# FPGA_GTP.net
KiCad netlist of a schematic drawn in Altium Designer
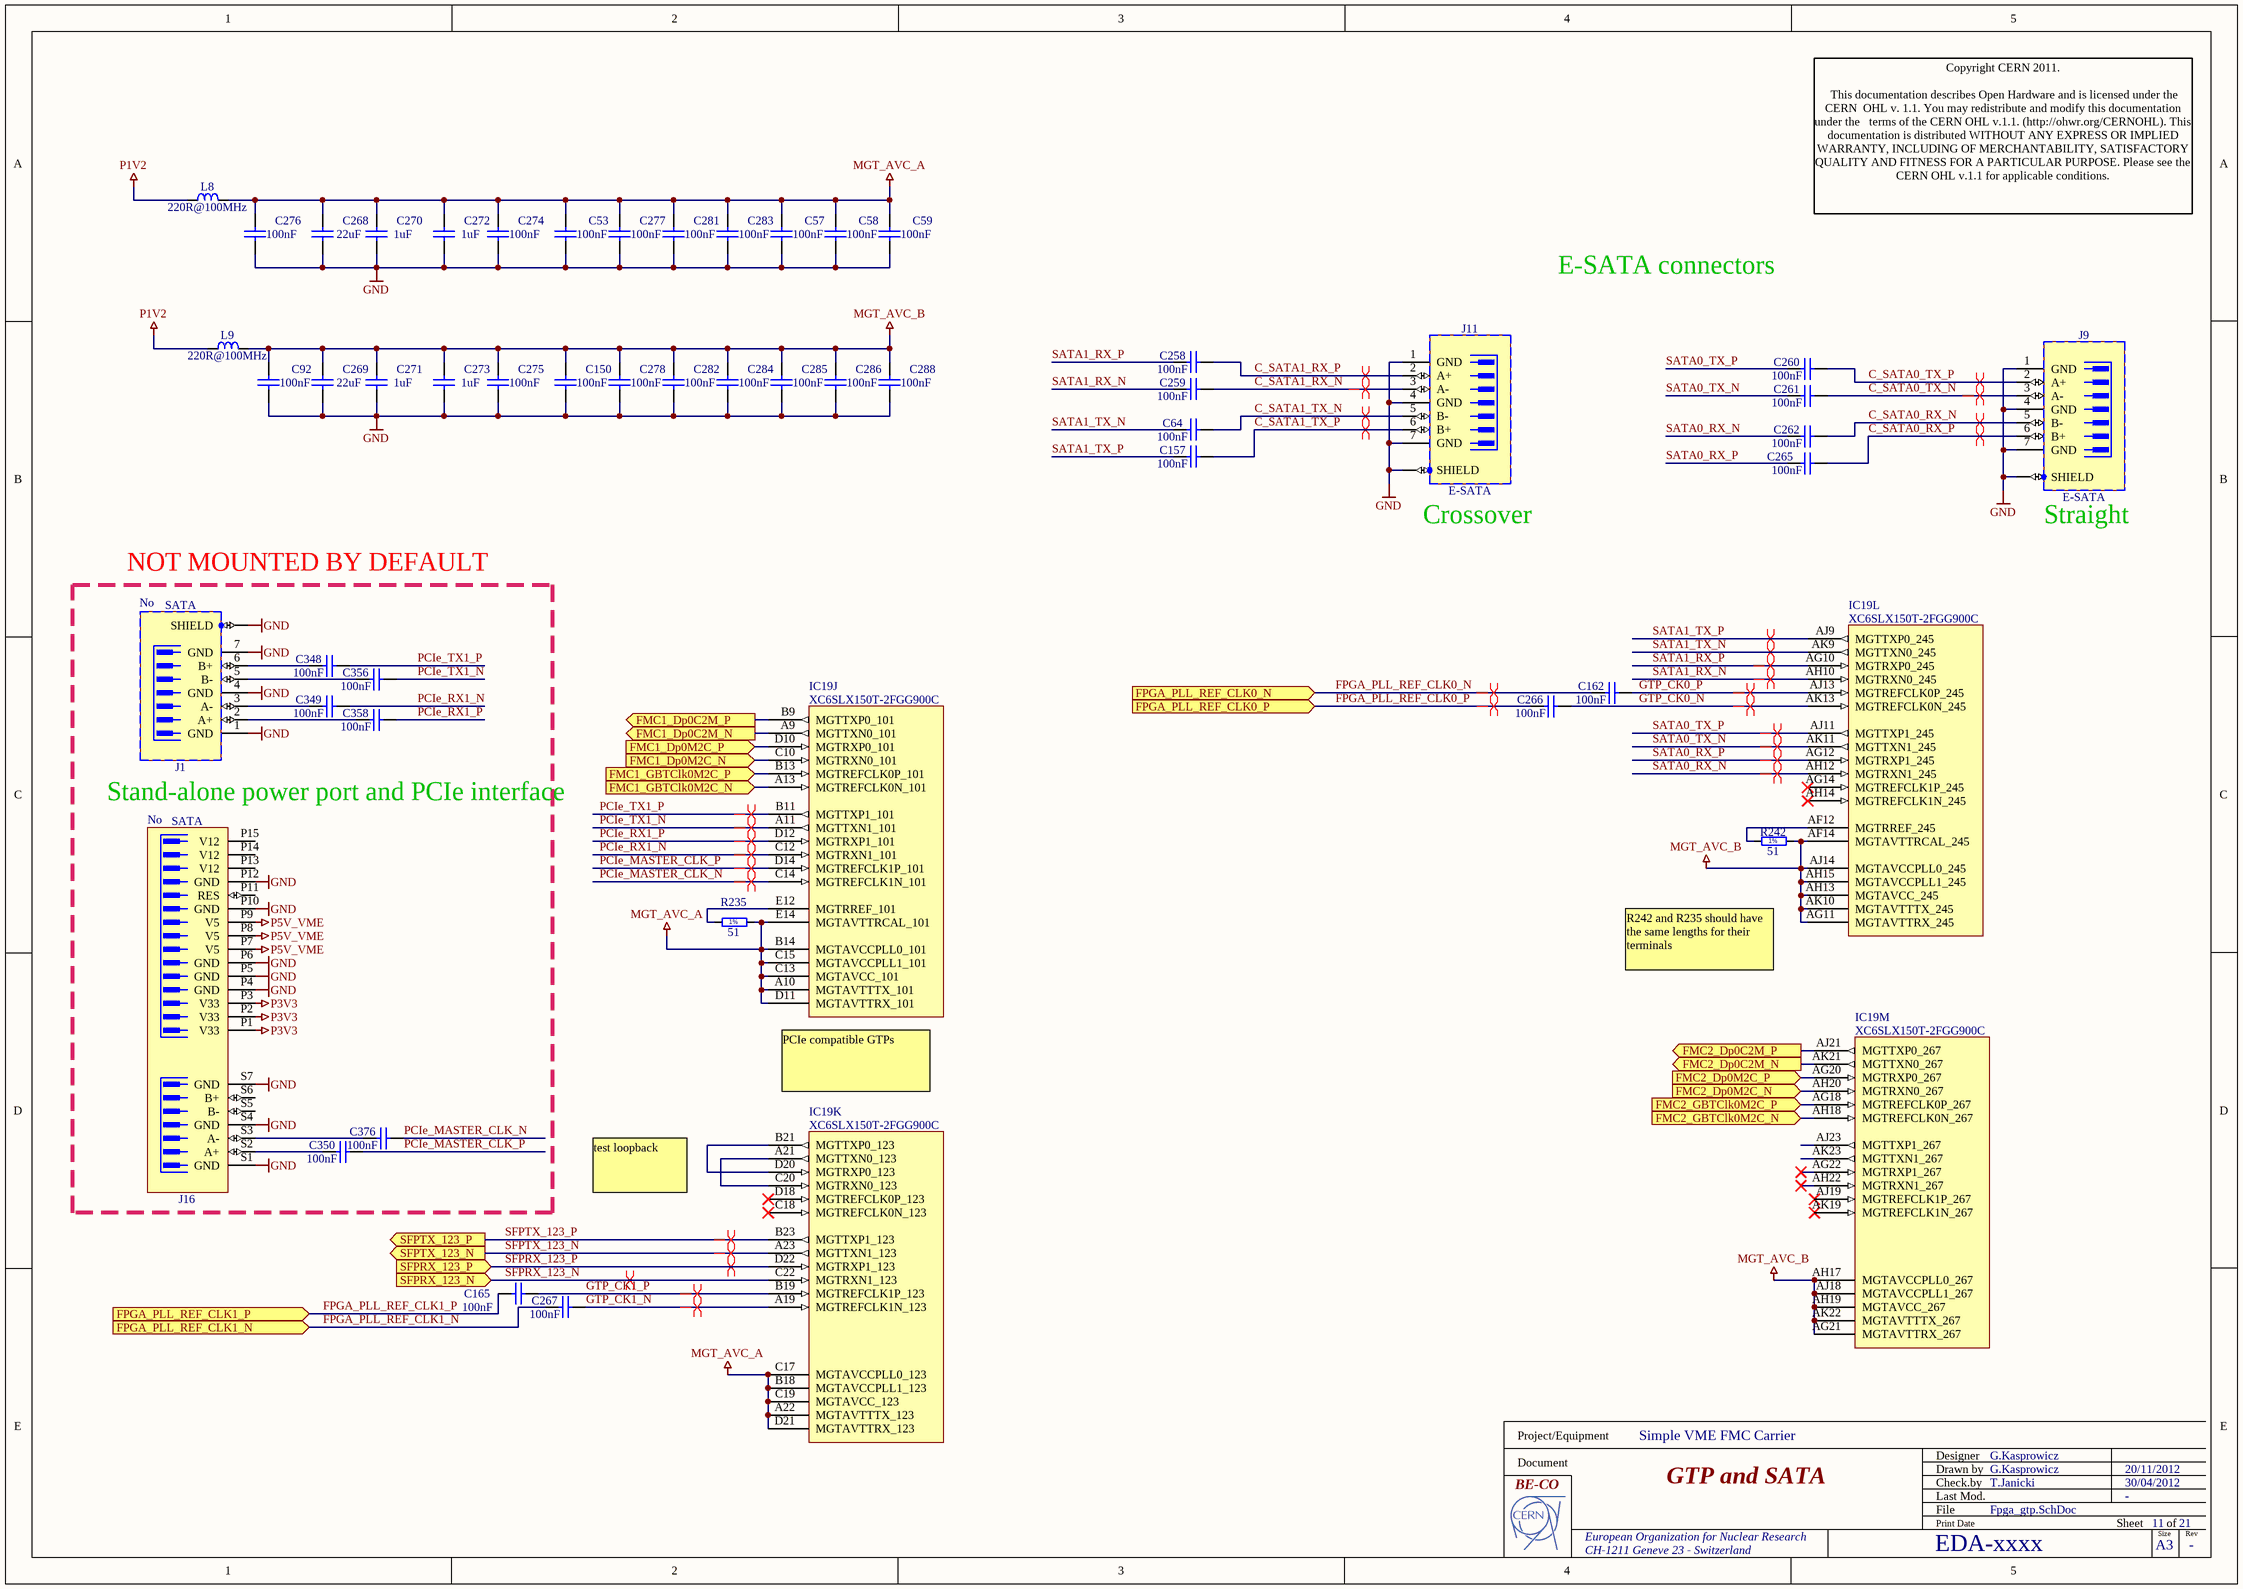
[diagram p0: FPGA_GTP.SchDoc]

(export (version "E")
  (design (tool "Eeschema 10.0.6"))
  (components
    (comp (ref "C53")
      (value "100nF")
      (footprint "CAPC1005X55N")
      (description "Non-polarised capacitor")
      (fields
        (field (name "PART NUMBER") "CC0402_100NF_16V_10%_X7R")
        (field (name "VOLTAGE") "16V")
        (field (name "AUTHOR") "CERN DEM JLC")
      )
      (libsource (lib "Capacitors") (part "Capacitor - non polarized"))
    )
    (comp (ref "C57")
      (value "100nF")
      (footprint "CAPC1005X55N")
      (description "Non-polarised capacitor")
      (fields
        (field (name "PART NUMBER") "CC0402_100NF_16V_10%_X7R")
        (field (name "VOLTAGE") "16V")
        (field (name "AUTHOR") "CERN DEM JLC")
      )
      (libsource (lib "Capacitors") (part "Capacitor - non polarized"))
    )
    (comp (ref "C58")
      (value "100nF")
      (footprint "CAPC1005X55N")
      (description "Non-polarised capacitor")
      (fields
        (field (name "PART NUMBER") "CC0402_100NF_16V_10%_X7R")
        (field (name "VOLTAGE") "16V")
        (field (name "AUTHOR") "CERN DEM JLC")
      )
      (libsource (lib "Capacitors") (part "Capacitor - non polarized"))
    )
    (comp (ref "C59")
      (value "100nF")
      (footprint "CAPC1005X55N")
      (description "Non-polarised capacitor")
      (fields
        (field (name "PART NUMBER") "CC0402_100NF_16V_10%_X7R")
        (field (name "VOLTAGE") "16V")
        (field (name "AUTHOR") "CERN DEM JLC")
      )
      (libsource (lib "Capacitors") (part "Capacitor - non polarized"))
    )
    (comp (ref "C64")
      (value "100nF")
      (footprint "CAPC1005X55N")
      (description "Non-polarised capacitor")
      (fields
        (field (name "PART NUMBER") "CC0402_100NF_16V_10%_X7R")
        (field (name "VOLTAGE") "16V")
        (field (name "AUTHOR") "CERN DEM JLC")
      )
      (libsource (lib "Capacitors") (part "Capacitor - non polarized"))
    )
    (comp (ref "C92")
      (value "100nF")
      (footprint "CAPC1005X55N")
      (description "Non-polarised capacitor")
      (fields
        (field (name "PART NUMBER") "CC0402_100NF_16V_10%_X7R")
        (field (name "VOLTAGE") "16V")
        (field (name "AUTHOR") "CERN DEM JLC")
      )
      (libsource (lib "Capacitors") (part "Capacitor - non polarized"))
    )
    (comp (ref "C150")
      (value "100nF")
      (footprint "CAPC1005X55N")
      (description "Non-polarised capacitor")
      (fields
        (field (name "PART NUMBER") "CC0402_100NF_16V_10%_X7R")
        (field (name "VOLTAGE") "16V")
        (field (name "AUTHOR") "CERN DEM JLC")
      )
      (libsource (lib "Capacitors") (part "Capacitor - non polarized"))
    )
    (comp (ref "C157")
      (value "100nF")
      (footprint "CAPC1005X55N")
      (description "Non-polarised capacitor")
      (fields
        (field (name "PART NUMBER") "CC0402_100NF_16V_10%_X7R")
        (field (name "VOLTAGE") "16V")
        (field (name "AUTHOR") "CERN DEM JLC")
      )
      (libsource (lib "Capacitors") (part "Capacitor - non polarized"))
    )
    (comp (ref "C162")
      (value "100nF")
      (footprint "CAPC1005X55N")
      (description "Non-polarised capacitor")
      (fields
        (field (name "PART NUMBER") "CC0402_100NF_16V_10%_X7R")
        (field (name "VOLTAGE") "16V")
        (field (name "AUTHOR") "CERN DEM JLC")
      )
      (libsource (lib "Capacitors") (part "Capacitor - non polarized"))
    )
    (comp (ref "C165")
      (value "100nF")
      (footprint "CAPC1005X55N")
      (description "Non-polarised capacitor")
      (fields
        (field (name "PART NUMBER") "CC0402_100NF_16V_10%_X7R")
        (field (name "VOLTAGE") "16V")
        (field (name "AUTHOR") "CERN DEM JLC")
      )
      (libsource (lib "Capacitors") (part "Capacitor - non polarized"))
    )
    (comp (ref "C258")
      (value "100nF")
      (footprint "CAPC1005X55N")
      (description "Non-polarised capacitor")
      (fields
        (field (name "PART NUMBER") "CC0402_100NF_16V_10%_X7R")
        (field (name "VOLTAGE") "16V")
        (field (name "AUTHOR") "CERN DEM JLC")
      )
      (libsource (lib "Capacitors") (part "Capacitor - non polarized"))
    )
    (comp (ref "C259")
      (value "100nF")
      (footprint "CAPC1005X55N")
      (description "Non-polarised capacitor")
      (fields
        (field (name "PART NUMBER") "CC0402_100NF_16V_10%_X7R")
        (field (name "VOLTAGE") "16V")
        (field (name "AUTHOR") "CERN DEM JLC")
      )
      (libsource (lib "Capacitors") (part "Capacitor - non polarized"))
    )
    (comp (ref "C260")
      (value "100nF")
      (footprint "CAPC1005X55N")
      (description "Non-polarised capacitor")
      (fields
        (field (name "PART NUMBER") "CC0402_100NF_16V_10%_X7R")
        (field (name "VOLTAGE") "16V")
        (field (name "AUTHOR") "CERN DEM JLC")
      )
      (libsource (lib "Capacitors") (part "Capacitor - non polarized"))
    )
    (comp (ref "C261")
      (value "100nF")
      (footprint "CAPC1005X55N")
      (description "Non-polarised capacitor")
      (fields
        (field (name "PART NUMBER") "CC0402_100NF_16V_10%_X7R")
        (field (name "VOLTAGE") "16V")
        (field (name "AUTHOR") "CERN DEM JLC")
      )
      (libsource (lib "Capacitors") (part "Capacitor - non polarized"))
    )
    (comp (ref "C262")
      (value "100nF")
      (footprint "CAPC1005X55N")
      (description "Non-polarised capacitor")
      (fields
        (field (name "PART NUMBER") "CC0402_100NF_16V_10%_X7R")
        (field (name "VOLTAGE") "16V")
        (field (name "AUTHOR") "CERN DEM JLC")
      )
      (libsource (lib "Capacitors") (part "Capacitor - non polarized"))
    )
    (comp (ref "C265")
      (value "100nF")
      (footprint "CAPC1005X55N")
      (description "Non-polarised capacitor")
      (fields
        (field (name "PART NUMBER") "CC0402_100NF_16V_10%_X7R")
        (field (name "VOLTAGE") "16V")
        (field (name "AUTHOR") "CERN DEM JLC")
      )
      (libsource (lib "Capacitors") (part "Capacitor - non polarized"))
    )
    (comp (ref "C266")
      (value "100nF")
      (footprint "CAPC1005X55N")
      (description "Non-polarised capacitor")
      (fields
        (field (name "PART NUMBER") "CC0402_100NF_16V_10%_X7R")
        (field (name "VOLTAGE") "16V")
        (field (name "AUTHOR") "CERN DEM JLC")
      )
      (libsource (lib "Capacitors") (part "Capacitor - non polarized"))
    )
    (comp (ref "C267")
      (value "100nF")
      (footprint "CAPC1005X55N")
      (description "Non-polarised capacitor")
      (fields
        (field (name "PART NUMBER") "CC0402_100NF_16V_10%_X7R")
        (field (name "VOLTAGE") "16V")
        (field (name "AUTHOR") "CERN DEM JLC")
      )
      (libsource (lib "Capacitors") (part "Capacitor - non polarized"))
    )
    (comp (ref "C268")
      (value "22uF")
      (footprint "CAPC3216X180N")
      (description "Non-polarised capacitor")
      (fields
        (field (name "PART NUMBER") "CC1206_22UF_10V_10%_X7R")
        (field (name "VOLTAGE") "10V")
        (field (name "AUTHOR") "CERN DEM JLC")
      )
      (libsource (lib "Capacitors") (part "Capacitor - non polarized"))
    )
    (comp (ref "C269")
      (value "22uF")
      (footprint "CAPC3216X180N")
      (description "Non-polarised capacitor")
      (fields
        (field (name "PART NUMBER") "CC1206_22UF_10V_10%_X7R")
        (field (name "VOLTAGE") "10V")
        (field (name "AUTHOR") "CERN DEM JLC")
      )
      (libsource (lib "Capacitors") (part "Capacitor - non polarized"))
    )
    (comp (ref "C270")
      (value "1uF")
      (footprint "CAPC1608X87N")
      (description "Non-polarised capacitor")
      (fields
        (field (name "PART NUMBER") "CC0603_1UF_16V_10%_X7R")
        (field (name "VOLTAGE") "16V")
        (field (name "AUTHOR") "CERN DEM JLC")
      )
      (libsource (lib "Capacitors") (part "Capacitor - non polarized"))
    )
    (comp (ref "C271")
      (value "1uF")
      (footprint "CAPC1608X87N")
      (description "Non-polarised capacitor")
      (fields
        (field (name "PART NUMBER") "CC0603_1UF_16V_10%_X7R")
        (field (name "VOLTAGE") "16V")
        (field (name "AUTHOR") "CERN DEM JLC")
      )
      (libsource (lib "Capacitors") (part "Capacitor - non polarized"))
    )
    (comp (ref "C272")
      (value "1uF")
      (footprint "CAPC1608X87N")
      (description "Non-polarised capacitor")
      (fields
        (field (name "PART NUMBER") "CC0603_1UF_16V_10%_X7R")
        (field (name "VOLTAGE") "16V")
        (field (name "AUTHOR") "CERN DEM JLC")
      )
      (libsource (lib "Capacitors") (part "Capacitor - non polarized"))
    )
    (comp (ref "C273")
      (value "1uF")
      (footprint "CAPC1608X87N")
      (description "Non-polarised capacitor")
      (fields
        (field (name "PART NUMBER") "CC0603_1UF_16V_10%_X7R")
        (field (name "VOLTAGE") "16V")
        (field (name "AUTHOR") "CERN DEM JLC")
      )
      (libsource (lib "Capacitors") (part "Capacitor - non polarized"))
    )
    (comp (ref "C274")
      (value "100nF")
      (footprint "CAPC1005X55N")
      (description "Non-polarised capacitor")
      (fields
        (field (name "PART NUMBER") "CC0402_100NF_16V_10%_X7R")
        (field (name "VOLTAGE") "16V")
        (field (name "AUTHOR") "CERN DEM JLC")
      )
      (libsource (lib "Capacitors") (part "Capacitor - non polarized"))
    )
    (comp (ref "C275")
      (value "100nF")
      (footprint "CAPC1005X55N")
      (description "Non-polarised capacitor")
      (fields
        (field (name "PART NUMBER") "CC0402_100NF_16V_10%_X7R")
        (field (name "VOLTAGE") "16V")
        (field (name "AUTHOR") "CERN DEM JLC")
      )
      (libsource (lib "Capacitors") (part "Capacitor - non polarized"))
    )
    (comp (ref "C276")
      (value "100nF")
      (footprint "CAPC1005X55N")
      (description "Non-polarised capacitor")
      (fields
        (field (name "PART NUMBER") "CC0402_100NF_16V_10%_X7R")
        (field (name "VOLTAGE") "16V")
        (field (name "AUTHOR") "CERN DEM JLC")
      )
      (libsource (lib "Capacitors") (part "Capacitor - non polarized"))
    )
    (comp (ref "C277")
      (value "100nF")
      (footprint "CAPC1005X55N")
      (description "Non-polarised capacitor")
      (fields
        (field (name "PART NUMBER") "CC0402_100NF_16V_10%_X7R")
        (field (name "VOLTAGE") "16V")
        (field (name "AUTHOR") "CERN DEM JLC")
      )
      (libsource (lib "Capacitors") (part "Capacitor - non polarized"))
    )
    (comp (ref "C278")
      (value "100nF")
      (footprint "CAPC1005X55N")
      (description "Non-polarised capacitor")
      (fields
        (field (name "PART NUMBER") "CC0402_100NF_16V_10%_X7R")
        (field (name "VOLTAGE") "16V")
        (field (name "AUTHOR") "CERN DEM JLC")
      )
      (libsource (lib "Capacitors") (part "Capacitor - non polarized"))
    )
    (comp (ref "C281")
      (value "100nF")
      (footprint "CAPC1005X55N")
      (description "Non-polarised capacitor")
      (fields
        (field (name "PART NUMBER") "CC0402_100NF_16V_10%_X7R")
        (field (name "VOLTAGE") "16V")
        (field (name "AUTHOR") "CERN DEM JLC")
      )
      (libsource (lib "Capacitors") (part "Capacitor - non polarized"))
    )
    (comp (ref "C282")
      (value "100nF")
      (footprint "CAPC1005X55N")
      (description "Non-polarised capacitor")
      (fields
        (field (name "PART NUMBER") "CC0402_100NF_16V_10%_X7R")
        (field (name "VOLTAGE") "16V")
        (field (name "AUTHOR") "CERN DEM JLC")
      )
      (libsource (lib "Capacitors") (part "Capacitor - non polarized"))
    )
    (comp (ref "C283")
      (value "100nF")
      (footprint "CAPC1005X55N")
      (description "Non-polarised capacitor")
      (fields
        (field (name "PART NUMBER") "CC0402_100NF_16V_10%_X7R")
        (field (name "VOLTAGE") "16V")
        (field (name "AUTHOR") "CERN DEM JLC")
      )
      (libsource (lib "Capacitors") (part "Capacitor - non polarized"))
    )
    (comp (ref "C284")
      (value "100nF")
      (footprint "CAPC1005X55N")
      (description "Non-polarised capacitor")
      (fields
        (field (name "PART NUMBER") "CC0402_100NF_16V_10%_X7R")
        (field (name "VOLTAGE") "16V")
        (field (name "AUTHOR") "CERN DEM JLC")
      )
      (libsource (lib "Capacitors") (part "Capacitor - non polarized"))
    )
    (comp (ref "C285")
      (value "100nF")
      (footprint "CAPC1005X55N")
      (description "Non-polarised capacitor")
      (fields
        (field (name "PART NUMBER") "CC0402_100NF_16V_10%_X7R")
        (field (name "VOLTAGE") "16V")
        (field (name "AUTHOR") "CERN DEM JLC")
      )
      (libsource (lib "Capacitors") (part "Capacitor - non polarized"))
    )
    (comp (ref "C286")
      (value "100nF")
      (footprint "CAPC1005X55N")
      (description "Non-polarised capacitor")
      (fields
        (field (name "PART NUMBER") "CC0402_100NF_16V_10%_X7R")
        (field (name "VOLTAGE") "16V")
        (field (name "AUTHOR") "CERN DEM JLC")
      )
      (libsource (lib "Capacitors") (part "Capacitor - non polarized"))
    )
    (comp (ref "C288")
      (value "100nF")
      (footprint "CAPC1005X55N")
      (description "Non-polarised capacitor")
      (fields
        (field (name "PART NUMBER") "CC0402_100NF_16V_10%_X7R")
        (field (name "VOLTAGE") "16V")
        (field (name "AUTHOR") "CERN DEM JLC")
      )
      (libsource (lib "Capacitors") (part "Capacitor - non polarized"))
    )
    (comp (ref "C348")
      (value "100nF")
      (footprint "CAPC1005X55N")
      (description "Non-polarised capacitor")
      (fields
        (field (name "PART NUMBER") "CC0402_100NF_16V_10%_X7R")
        (field (name "VOLTAGE") "16V")
        (field (name "AUTHOR") "CERN DEM JLC")
      )
      (libsource (lib "Capacitors") (part "Capacitor - non polarized"))
    )
    (comp (ref "C349")
      (value "100nF")
      (footprint "CAPC1005X55N")
      (description "Non-polarised capacitor")
      (fields
        (field (name "PART NUMBER") "CC0402_100NF_16V_10%_X7R")
        (field (name "VOLTAGE") "16V")
        (field (name "AUTHOR") "CERN DEM JLC")
      )
      (libsource (lib "Capacitors") (part "Capacitor - non polarized"))
    )
    (comp (ref "C350")
      (value "100nF")
      (footprint "CAPC1005X55N")
      (description "Non-polarised capacitor")
      (fields
        (field (name "PART NUMBER") "CC0402_100NF_16V_10%_X7R")
        (field (name "VOLTAGE") "16V")
        (field (name "AUTHOR") "CERN DEM JLC")
      )
      (libsource (lib "Capacitors") (part "Capacitor - non polarized"))
    )
    (comp (ref "C356")
      (value "100nF")
      (footprint "CAPC1005X55N")
      (description "Non-polarised capacitor")
      (fields
        (field (name "PART NUMBER") "CC0402_100NF_16V_10%_X7R")
        (field (name "VOLTAGE") "16V")
        (field (name "AUTHOR") "CERN DEM JLC")
      )
      (libsource (lib "Capacitors") (part "Capacitor - non polarized"))
    )
    (comp (ref "C358")
      (value "100nF")
      (footprint "CAPC1005X55N")
      (description "Non-polarised capacitor")
      (fields
        (field (name "PART NUMBER") "CC0402_100NF_16V_10%_X7R")
        (field (name "VOLTAGE") "16V")
        (field (name "AUTHOR") "CERN DEM JLC")
      )
      (libsource (lib "Capacitors") (part "Capacitor - non polarized"))
    )
    (comp (ref "C376")
      (value "100nF")
      (footprint "CAPC1005X55N")
      (description "Non-polarised capacitor")
      (fields
        (field (name "PART NUMBER") "CC0402_100NF_16V_10%_X7R")
        (field (name "VOLTAGE") "16V")
        (field (name "AUTHOR") "CERN DEM JLC")
      )
      (libsource (lib "Capacitors") (part "Capacitor - non polarized"))
    )
    (comp (ref "IC19")
      (value "XC6SLX150T-2FGG900C")
      (footprint "BGA900C100P30X30_3100X3100X260")
      (description "SPARTAN-6, FPGA, 900-Ball BGA, Commercial Grade, Pb-Free")
      (fields (field (name "MANUFACTURER") "XILINX") (field (name "AUTHOR") "CERN DEM JLC"))
      (libsource (lib "ICs And Semiconductors") (part "XC6SLX150T-2FGG900C"))
    )
    (comp (ref "J1")
      (value "SATA")
      (footprint "3M_5607-4200-SH")
      (description "7 Pin + 1 Shield SATA Receptacle")
      (fields
        (field (name "PART NUMBER") "3M_5607-4200-SH")
        (field (name "MOUNTED") "No")
        (field (name "MANUFACTURER") "3M")
        (field (name "AUTHOR") "CERN DEM JLC")
      )
      (libsource (lib "") (part "Connector SATA 7 Male + 1 Shield_1"))
    )
    (comp (ref "J9")
      (value "E-SATA")
      (footprint "FCI_10074141-001LF")
      (description "7 Pin + 1 Shield SATA Receptacle")
      (fields
        (field (name "PART NUMBER") "FCI_10074141-001LF")
        (field (name "MANUFACTURER") "FCI")
        (field (name "AUTHOR") "CERN DEM JLC")
      )
      (libsource (lib "Connectors") (part "Connector SATA 7 Male + 1 Shield"))
    )
    (comp (ref "J11")
      (value "E-SATA")
      (footprint "FCI_10074141-001LF")
      (description "7 Pin + 1 Shield SATA Receptacle")
      (fields
        (field (name "PART NUMBER") "FCI_10074141-001LF")
        (field (name "MANUFACTURER") "FCI")
        (field (name "AUTHOR") "CERN DEM JLC")
      )
      (libsource (lib "Connectors") (part "Connector SATA 7 Male + 1 Shield"))
    )
    (comp (ref "J16")
      (value "SATA")
      (footprint "MOLEX_87703-0001")
      (description "7 Signal Pin + 15 Power Pin SATA Connecteur")
      (fields
        (field (name "PART NUMBER") "MOLEX_87703-0001")
        (field (name "MOUNTED") "No")
        (field (name "MANUFACTURER") "MOLEX")
        (field (name "AUTHOR") "CERN DEM JLC")
      )
      (libsource (lib "Connectors") (part "Connector SATA 7 + 15 Male"))
    )
    (comp (ref "L8")
      (value "220R@100MHz")
      (footprint "INDC2012X105N")
      (description "Inductor")
      (fields
        (field (name "PART NUMBER") "IND0805_MURATA_BLM21PG221SN1D")
        (field (name "POWER") "2A")
        (field (name "AUTHOR") "CERN DEM JLC")
      )
      (libsource (lib "Inductors & Transformers") (part "Inductor"))
    )
    (comp (ref "L9")
      (value "220R@100MHz")
      (footprint "INDC2012X105N")
      (description "Inductor")
      (fields
        (field (name "PART NUMBER") "IND0805_MURATA_BLM21PG221SN1D")
        (field (name "POWER") "2A")
        (field (name "AUTHOR") "CERN DEM JLC")
      )
      (libsource (lib "Inductors & Transformers") (part "Inductor"))
    )
    (comp (ref "R235")
      (value "51")
      (footprint "RESC1005X40N")
      (description "Resistor - 1%")
      (fields
        (field (name "PART NUMBER") "R0402_51R_1%_0.0625W_100PPM")
        (field (name "POWER") "0.0625W")
        (field (name "AUTHOR") "CERN DEM JLC")
      )
      (libsource (lib "Resistors") (part "Resistor - 1%"))
    )
    (comp (ref "R242")
      (value "51")
      (footprint "RESC1005X40N")
      (description "Resistor - 1%")
      (fields
        (field (name "PART NUMBER") "R0402_51R_1%_0.0625W_100PPM")
        (field (name "POWER") "0.0625W")
        (field (name "AUTHOR") "CERN DEM JLC")
      )
      (libsource (lib "Resistors") (part "Resistor - 1%"))
    )
  )
  (nets
    (net (code "1") (name "/C_SATA0_RX_N") (class "Default")
      (node (ref "C262") (pin "2") (pinfunction "2_2") (pintype "passive"))
      (node (ref "J9") (pin "5") (pinfunction "B-_5") (pintype "bidirectional"))
    )
    (net (code "2") (name "/C_SATA0_RX_P") (class "Default")
      (node (ref "C265") (pin "2") (pinfunction "2_2") (pintype "passive"))
      (node (ref "J9") (pin "6") (pinfunction "B+_6") (pintype "bidirectional"))
    )
    (net (code "3") (name "/C_SATA0_TX_N") (class "Default")
      (node (ref "C261") (pin "2") (pinfunction "2_2") (pintype "passive"))
      (node (ref "J9") (pin "3") (pinfunction "A-_3") (pintype "bidirectional"))
    )
    (net (code "4") (name "/C_SATA0_TX_P") (class "Default")
      (node (ref "C260") (pin "2") (pinfunction "2_2") (pintype "passive"))
      (node (ref "J9") (pin "2") (pinfunction "A+_2") (pintype "bidirectional"))
    )
    (net (code "5") (name "/C_SATA1_RX_N") (class "Default")
      (node (ref "C259") (pin "2") (pinfunction "2_2") (pintype "passive"))
      (node (ref "J11") (pin "3") (pinfunction "A-_3") (pintype "bidirectional"))
    )
    (net (code "6") (name "/C_SATA1_RX_P") (class "Default")
      (node (ref "C258") (pin "2") (pinfunction "2_2") (pintype "passive"))
      (node (ref "J11") (pin "2") (pinfunction "A+_2") (pintype "bidirectional"))
    )
    (net (code "7") (name "/C_SATA1_TX_N") (class "Default")
      (node (ref "C64") (pin "2") (pinfunction "2_2") (pintype "passive"))
      (node (ref "J11") (pin "5") (pinfunction "B-_5") (pintype "bidirectional"))
    )
    (net (code "8") (name "/C_SATA1_TX_P") (class "Default")
      (node (ref "C157") (pin "2") (pinfunction "2_2") (pintype "passive"))
      (node (ref "J11") (pin "6") (pinfunction "B+_6") (pintype "bidirectional"))
    )
    (net (code "9") (name "/FMC1_Dp0C2M_N") (class "Default")
      (node (ref "IC19") (pin "A9") (pinfunction "MGTTXN0_101_A9") (pintype "output"))
    )
    (net (code "10") (name "/FMC1_Dp0C2M_P") (class "Default")
      (node (ref "IC19") (pin "B9") (pinfunction "MGTTXP0_101_B9") (pintype "output"))
    )
    (net (code "11") (name "/FMC1_Dp0M2C_N") (class "Default")
      (node (ref "IC19") (pin "C10") (pinfunction "MGTRXN0_101_C10") (pintype "input"))
    )
    (net (code "12") (name "/FMC1_Dp0M2C_P") (class "Default")
      (node (ref "IC19") (pin "D10") (pinfunction "MGTRXP0_101_D10") (pintype "input"))
    )
    (net (code "13") (name "/FMC1_GBTClk0M2C_N") (class "Default")
      (node (ref "IC19") (pin "A13") (pinfunction "MGTREFCLK0N_101_A13") (pintype "input"))
    )
    (net (code "14") (name "/FMC1_GBTClk0M2C_P") (class "Default")
      (node (ref "IC19") (pin "B13") (pinfunction "MGTREFCLK0P_101_B13") (pintype "input"))
    )
    (net (code "15") (name "/FMC2_Dp0C2M_N") (class "Default")
      (node (ref "IC19") (pin "AK21") (pinfunction "MGTTXN0_267_AK21") (pintype "output"))
    )
    (net (code "16") (name "/FMC2_Dp0C2M_P") (class "Default")
      (node (ref "IC19") (pin "AJ21") (pinfunction "MGTTXP0_267_AJ21") (pintype "output"))
    )
    (net (code "17") (name "/FMC2_Dp0M2C_N") (class "Default")
      (node (ref "IC19") (pin "AH20") (pinfunction "MGTRXN0_267_AH20") (pintype "input"))
    )
    (net (code "18") (name "/FMC2_Dp0M2C_P") (class "Default")
      (node (ref "IC19") (pin "AG20") (pinfunction "MGTRXP0_267_AG20") (pintype "input"))
    )
    (net (code "19") (name "/FMC2_GBTClk0M2C_N") (class "Default")
      (node (ref "IC19") (pin "AH18") (pinfunction "MGTREFCLK0N_267_AH18") (pintype "input"))
    )
    (net (code "20") (name "/FMC2_GBTClk0M2C_P") (class "Default")
      (node (ref "IC19") (pin "AG18") (pinfunction "MGTREFCLK0P_267_AG18") (pintype "input"))
    )
    (net (code "21") (name "/FPGA_PLL_REF_CLK0_N") (class "Default")
      (node (ref "C162") (pin "1") (pinfunction "1_1") (pintype "passive"))
    )
    (net (code "22") (name "/FPGA_PLL_REF_CLK0_P") (class "Default")
      (node (ref "C266") (pin "1") (pinfunction "1_1") (pintype "passive"))
    )
    (net (code "23") (name "/FPGA_PLL_REF_CLK1_N") (class "Default")
      (node (ref "C267") (pin "1") (pinfunction "1_1") (pintype "passive"))
    )
    (net (code "24") (name "/FPGA_PLL_REF_CLK1_P") (class "Default")
      (node (ref "C165") (pin "1") (pinfunction "1_1") (pintype "passive"))
    )
    (net (code "25") (name "/GTP_CK0_N") (class "Default")
      (node (ref "C266") (pin "2") (pinfunction "2_2") (pintype "passive"))
      (node (ref "IC19") (pin "AK13") (pinfunction "MGTREFCLK0N_245_AK13") (pintype "input"))
    )
    (net (code "26") (name "/GTP_CK0_P") (class "Default")
      (node (ref "C162") (pin "2") (pinfunction "2_2") (pintype "passive"))
      (node (ref "IC19") (pin "AJ13") (pinfunction "MGTREFCLK0P_245_AJ13") (pintype "input"))
    )
    (net (code "27") (name "/GTP_CK1_N") (class "Default")
      (node (ref "C267") (pin "2") (pinfunction "2_2") (pintype "passive"))
      (node (ref "IC19") (pin "A19") (pinfunction "MGTREFCLK1N_123_A19") (pintype "input"))
    )
    (net (code "28") (name "/GTP_CK1_P") (class "Default")
      (node (ref "C165") (pin "2") (pinfunction "2_2") (pintype "passive"))
      (node (ref "IC19") (pin "B19") (pinfunction "MGTREFCLK1P_123_B19") (pintype "input"))
    )
    (net (code "29") (name "/PCIe_MASTER_CLK_N") (class "Default")
      (node (ref "C376") (pin "2") (pinfunction "2_2") (pintype "passive"))
      (node (ref "IC19") (pin "C14") (pinfunction "MGTREFCLK1N_101_C14") (pintype "input"))
    )
    (net (code "30") (name "/PCIe_MASTER_CLK_P") (class "Default")
      (node (ref "C350") (pin "2") (pinfunction "2_2") (pintype "passive"))
      (node (ref "IC19") (pin "D14") (pinfunction "MGTREFCLK1P_101_D14") (pintype "input"))
    )
    (net (code "31") (name "/PCIe_RX1_N") (class "Default")
      (node (ref "C349") (pin "2") (pinfunction "2_2") (pintype "passive"))
      (node (ref "IC19") (pin "C12") (pinfunction "MGTRXN1_101_C12") (pintype "input"))
    )
    (net (code "32") (name "/PCIe_RX1_P") (class "Default")
      (node (ref "C358") (pin "2") (pinfunction "2_2") (pintype "passive"))
      (node (ref "IC19") (pin "D12") (pinfunction "MGTRXP1_101_D12") (pintype "input"))
    )
    (net (code "33") (name "/PCIe_TX1_N") (class "Default")
      (node (ref "C356") (pin "2") (pinfunction "2_2") (pintype "passive"))
      (node (ref "IC19") (pin "A11") (pinfunction "MGTTXN1_101_A11") (pintype "output"))
    )
    (net (code "34") (name "/PCIe_TX1_P") (class "Default")
      (node (ref "C348") (pin "2") (pinfunction "2_2") (pintype "passive"))
      (node (ref "IC19") (pin "B11") (pinfunction "MGTTXP1_101_B11") (pintype "output"))
    )
    (net (code "35") (name "/SATA0_RX_N") (class "Default")
      (node (ref "C262") (pin "1") (pinfunction "1_1") (pintype "passive"))
      (node (ref "IC19") (pin "AH12") (pinfunction "MGTRXN1_245_AH12") (pintype "input"))
    )
    (net (code "36") (name "/SATA0_RX_P") (class "Default")
      (node (ref "C265") (pin "1") (pinfunction "1_1") (pintype "passive"))
      (node (ref "IC19") (pin "AG12") (pinfunction "MGTRXP1_245_AG12") (pintype "input"))
    )
    (net (code "37") (name "/SATA0_TX_N") (class "Default")
      (node (ref "C261") (pin "1") (pinfunction "1_1") (pintype "passive"))
      (node (ref "IC19") (pin "AK11") (pinfunction "MGTTXN1_245_AK11") (pintype "output"))
    )
    (net (code "38") (name "/SATA0_TX_P") (class "Default")
      (node (ref "C260") (pin "1") (pinfunction "1_1") (pintype "passive"))
      (node (ref "IC19") (pin "AJ11") (pinfunction "MGTTXP1_245_AJ11") (pintype "output"))
    )
    (net (code "39") (name "/SATA1_RX_N") (class "Default")
      (node (ref "C259") (pin "1") (pinfunction "1_1") (pintype "passive"))
      (node (ref "IC19") (pin "AH10") (pinfunction "MGTRXN0_245_AH10") (pintype "input"))
    )
    (net (code "40") (name "/SATA1_RX_P") (class "Default")
      (node (ref "C258") (pin "1") (pinfunction "1_1") (pintype "passive"))
      (node (ref "IC19") (pin "AG10") (pinfunction "MGTRXP0_245_AG10") (pintype "input"))
    )
    (net (code "41") (name "/SATA1_TX_N") (class "Default")
      (node (ref "C64") (pin "1") (pinfunction "1_1") (pintype "passive"))
      (node (ref "IC19") (pin "AK9") (pinfunction "MGTTXN0_245_AK9") (pintype "output"))
    )
    (net (code "42") (name "/SATA1_TX_P") (class "Default")
      (node (ref "C157") (pin "1") (pinfunction "1_1") (pintype "passive"))
      (node (ref "IC19") (pin "AJ9") (pinfunction "MGTTXP0_245_AJ9") (pintype "output"))
    )
    (net (code "43") (name "/SFPRX_123_N") (class "Default")
      (node (ref "IC19") (pin "C22") (pinfunction "MGTRXN1_123_C22") (pintype "input"))
    )
    (net (code "44") (name "/SFPRX_123_P") (class "Default")
      (node (ref "IC19") (pin "D22") (pinfunction "MGTRXP1_123_D22") (pintype "input"))
    )
    (net (code "45") (name "/SFPTX_123_N") (class "Default")
      (node (ref "IC19") (pin "A23") (pinfunction "MGTTXN1_123_A23") (pintype "output"))
    )
    (net (code "46") (name "/SFPTX_123_P") (class "Default")
      (node (ref "IC19") (pin "B23") (pinfunction "MGTTXP1_123_B23") (pintype "output"))
    )
    (net (code "47") (name "GND") (class "Default")
      (node (ref "C150") (pin "1") (pinfunction "1_1") (pintype "passive"))
      (node (ref "C268") (pin "1") (pinfunction "1_1") (pintype "passive"))
      (node (ref "C269") (pin "1") (pinfunction "1_1") (pintype "passive"))
      (node (ref "C270") (pin "1") (pinfunction "1_1") (pintype "passive"))
      (node (ref "C271") (pin "1") (pinfunction "1_1") (pintype "passive"))
      (node (ref "C272") (pin "1") (pinfunction "1_1") (pintype "passive"))
      (node (ref "C273") (pin "1") (pinfunction "1_1") (pintype "passive"))
      (node (ref "C274") (pin "1") (pinfunction "1_1") (pintype "passive"))
      (node (ref "C275") (pin "1") (pinfunction "1_1") (pintype "passive"))
      (node (ref "C276") (pin "1") (pinfunction "1_1") (pintype "passive"))
      (node (ref "C277") (pin "1") (pinfunction "1_1") (pintype "passive"))
      (node (ref "C278") (pin "1") (pinfunction "1_1") (pintype "passive"))
      (node (ref "C281") (pin "1") (pinfunction "1_1") (pintype "passive"))
      (node (ref "C282") (pin "1") (pinfunction "1_1") (pintype "passive"))
      (node (ref "C283") (pin "1") (pinfunction "1_1") (pintype "passive"))
      (node (ref "C284") (pin "1") (pinfunction "1_1") (pintype "passive"))
      (node (ref "C285") (pin "1") (pinfunction "1_1") (pintype "passive"))
      (node (ref "C286") (pin "1") (pinfunction "1_1") (pintype "passive"))
      (node (ref "C288") (pin "1") (pinfunction "1_1") (pintype "passive"))
      (node (ref "C53") (pin "1") (pinfunction "1_1") (pintype "passive"))
      (node (ref "C57") (pin "1") (pinfunction "1_1") (pintype "passive"))
      (node (ref "C58") (pin "1") (pinfunction "1_1") (pintype "passive"))
      (node (ref "C59") (pin "1") (pinfunction "1_1") (pintype "passive"))
      (node (ref "C92") (pin "1") (pinfunction "1_1") (pintype "passive"))
      (node (ref "J1") (pin "1") (pinfunction "GND_1") (pintype "power_in"))
      (node (ref "J1") (pin "4") (pinfunction "GND_4") (pintype "power_in"))
      (node (ref "J1") (pin "7") (pinfunction "GND_7") (pintype "power_in"))
      (node (ref "J1") (pin "8") (pinfunction "SHIELD_8") (pintype "bidirectional"))
      (node (ref "J11") (pin "1") (pinfunction "GND_1") (pintype "power_in"))
      (node (ref "J11") (pin "4") (pinfunction "GND_4") (pintype "power_in"))
      (node (ref "J11") (pin "7") (pinfunction "GND_7") (pintype "power_in"))
      (node (ref "J11") (pin "8") (pinfunction "SHIELD_8") (pintype "bidirectional"))
      (node (ref "J16") (pin "P10") (pinfunction "GND_P10") (pintype "power_in"))
      (node (ref "J16") (pin "P12") (pinfunction "GND_P12") (pintype "power_in"))
      (node (ref "J16") (pin "P4") (pinfunction "GND_P4") (pintype "power_in"))
      (node (ref "J16") (pin "P5") (pinfunction "GND_P5") (pintype "power_in"))
      (node (ref "J16") (pin "P6") (pinfunction "GND_P6") (pintype "power_in"))
      (node (ref "J16") (pin "S1") (pinfunction "GND_S1") (pintype "power_in"))
      (node (ref "J16") (pin "S4") (pinfunction "GND_S4") (pintype "power_in"))
      (node (ref "J16") (pin "S7") (pinfunction "GND_S7") (pintype "power_in"))
      (node (ref "J9") (pin "1") (pinfunction "GND_1") (pintype "power_in"))
      (node (ref "J9") (pin "4") (pinfunction "GND_4") (pintype "power_in"))
      (node (ref "J9") (pin "7") (pinfunction "GND_7") (pintype "power_in"))
      (node (ref "J9") (pin "8") (pinfunction "SHIELD_8") (pintype "bidirectional"))
    )
    (net (code "48") (name "MGT_AVC_A") (class "Default")
      (node (ref "C268") (pin "2") (pinfunction "2_2") (pintype "passive"))
      (node (ref "C270") (pin "2") (pinfunction "2_2") (pintype "passive"))
      (node (ref "C272") (pin "2") (pinfunction "2_2") (pintype "passive"))
      (node (ref "C274") (pin "2") (pinfunction "2_2") (pintype "passive"))
      (node (ref "C276") (pin "2") (pinfunction "2_2") (pintype "passive"))
      (node (ref "C277") (pin "2") (pinfunction "2_2") (pintype "passive"))
      (node (ref "C281") (pin "2") (pinfunction "2_2") (pintype "passive"))
      (node (ref "C283") (pin "2") (pinfunction "2_2") (pintype "passive"))
      (node (ref "C53") (pin "2") (pinfunction "2_2") (pintype "passive"))
      (node (ref "C57") (pin "2") (pinfunction "2_2") (pintype "passive"))
      (node (ref "C58") (pin "2") (pinfunction "2_2") (pintype "passive"))
      (node (ref "C59") (pin "2") (pinfunction "2_2") (pintype "passive"))
      (node (ref "IC19") (pin "A10") (pinfunction "MGTAVTTTX_101_A10") (pintype "power_in"))
      (node (ref "IC19") (pin "A22") (pinfunction "MGTAVTTTX_123_A22") (pintype "power_in"))
      (node (ref "IC19") (pin "B14") (pinfunction "MGTAVCCPLL0_101_B14") (pintype "power_in"))
      (node (ref "IC19") (pin "B18") (pinfunction "MGTAVCCPLL1_123_B18") (pintype "power_in"))
      (node (ref "IC19") (pin "C13") (pinfunction "MGTAVCC_101_C13") (pintype "power_in"))
      (node (ref "IC19") (pin "C15") (pinfunction "MGTAVCCPLL1_101_C15") (pintype "power_in"))
      (node (ref "IC19") (pin "C17") (pinfunction "MGTAVCCPLL0_123_C17") (pintype "power_in"))
      (node (ref "IC19") (pin "C19") (pinfunction "MGTAVCC_123_C19") (pintype "power_in"))
      (node (ref "IC19") (pin "D11") (pinfunction "MGTAVTTRX_101_D11") (pintype "power_in"))
      (node (ref "IC19") (pin "D21") (pinfunction "MGTAVTTRX_123_D21") (pintype "power_in"))
      (node (ref "IC19") (pin "E14") (pinfunction "MGTAVTTRCAL_101_E14") (pintype "power_in"))
      (node (ref "L8") (pin "2") (pinfunction "2_2") (pintype "passive"))
      (node (ref "R235") (pin "2") (pinfunction "2_2") (pintype "passive"))
    )
    (net (code "49") (name "MGT_AVC_B") (class "Default")
      (node (ref "C150") (pin "2") (pinfunction "2_2") (pintype "passive"))
      (node (ref "C269") (pin "2") (pinfunction "2_2") (pintype "passive"))
      (node (ref "C271") (pin "2") (pinfunction "2_2") (pintype "passive"))
      (node (ref "C273") (pin "2") (pinfunction "2_2") (pintype "passive"))
      (node (ref "C275") (pin "2") (pinfunction "2_2") (pintype "passive"))
      (node (ref "C278") (pin "2") (pinfunction "2_2") (pintype "passive"))
      (node (ref "C282") (pin "2") (pinfunction "2_2") (pintype "passive"))
      (node (ref "C284") (pin "2") (pinfunction "2_2") (pintype "passive"))
      (node (ref "C285") (pin "2") (pinfunction "2_2") (pintype "passive"))
      (node (ref "C286") (pin "2") (pinfunction "2_2") (pintype "passive"))
      (node (ref "C288") (pin "2") (pinfunction "2_2") (pintype "passive"))
      (node (ref "C92") (pin "2") (pinfunction "2_2") (pintype "passive"))
      (node (ref "IC19") (pin "AF14") (pinfunction "MGTAVTTRCAL_245_AF14") (pintype "power_in"))
      (node (ref "IC19") (pin "AG11") (pinfunction "MGTAVTTRX_245_AG11") (pintype "power_in"))
      (node (ref "IC19") (pin "AG21") (pinfunction "MGTAVTTRX_267_AG21") (pintype "power_in"))
      (node (ref "IC19") (pin "AH13") (pinfunction "MGTAVCC_245_AH13") (pintype "power_in"))
      (node (ref "IC19") (pin "AH15") (pinfunction "MGTAVCCPLL1_245_AH15") (pintype "power_in"))
      (node (ref "IC19") (pin "AH17") (pinfunction "MGTAVCCPLL0_267_AH17") (pintype "power_in"))
      (node (ref "IC19") (pin "AH19") (pinfunction "MGTAVCC_267_AH19") (pintype "power_in"))
      (node (ref "IC19") (pin "AJ14") (pinfunction "MGTAVCCPLL0_245_AJ14") (pintype "power_in"))
      (node (ref "IC19") (pin "AJ18") (pinfunction "MGTAVCCPLL1_267_AJ18") (pintype "power_in"))
      (node (ref "IC19") (pin "AK10") (pinfunction "MGTAVTTTX_245_AK10") (pintype "power_in"))
      (node (ref "IC19") (pin "AK22") (pinfunction "MGTAVTTTX_267_AK22") (pintype "power_in"))
      (node (ref "L9") (pin "2") (pinfunction "2_2") (pintype "passive"))
      (node (ref "R242") (pin "2") (pinfunction "2_2") (pintype "passive"))
    )
    (net (code "50") (name "Net-(IC19J-MGTRREF_101)") (class "Default")
      (node (ref "IC19") (pin "E12") (pinfunction "MGTRREF_101_E12") (pintype "power_in"))
      (node (ref "R235") (pin "1") (pinfunction "1_1") (pintype "passive"))
    )
    (net (code "51") (name "Net-(IC19K-MGTRXN0_123)") (class "Default")
      (node (ref "IC19") (pin "A21") (pinfunction "MGTTXN0_123_A21") (pintype "output"))
      (node (ref "IC19") (pin "C20") (pinfunction "MGTRXN0_123_C20") (pintype "input"))
    )
    (net (code "52") (name "Net-(IC19K-MGTRXP0_123)") (class "Default")
      (node (ref "IC19") (pin "B21") (pinfunction "MGTTXP0_123_B21") (pintype "output"))
      (node (ref "IC19") (pin "D20") (pinfunction "MGTRXP0_123_D20") (pintype "input"))
    )
    (net (code "53") (name "Net-(IC19L-MGTRREF_245)") (class "Default")
      (node (ref "IC19") (pin "AF12") (pinfunction "MGTRREF_245_AF12") (pintype "power_in"))
      (node (ref "R242") (pin "1") (pinfunction "1_1") (pintype "passive"))
    )
    (net (code "54") (name "Net-(J1-A+)") (class "Default")
      (node (ref "C358") (pin "1") (pinfunction "1_1") (pintype "passive"))
      (node (ref "J1") (pin "2") (pinfunction "A+_2") (pintype "bidirectional"))
    )
    (net (code "55") (name "Net-(J1-A-)") (class "Default")
      (node (ref "C349") (pin "1") (pinfunction "1_1") (pintype "passive"))
      (node (ref "J1") (pin "3") (pinfunction "A-_3") (pintype "bidirectional"))
    )
    (net (code "56") (name "Net-(J1-B+)") (class "Default")
      (node (ref "C348") (pin "1") (pinfunction "1_1") (pintype "passive"))
      (node (ref "J1") (pin "6") (pinfunction "B+_6") (pintype "bidirectional"))
    )
    (net (code "57") (name "Net-(J1-B-)") (class "Default")
      (node (ref "C356") (pin "1") (pinfunction "1_1") (pintype "passive"))
      (node (ref "J1") (pin "5") (pinfunction "B-_5") (pintype "bidirectional"))
    )
    (net (code "58") (name "Net-(J16-A+)") (class "Default")
      (node (ref "C350") (pin "1") (pinfunction "1_1") (pintype "passive"))
      (node (ref "J16") (pin "S2") (pinfunction "A+_S2") (pintype "bidirectional"))
    )
    (net (code "59") (name "Net-(J16-A-)") (class "Default")
      (node (ref "C376") (pin "1") (pinfunction "1_1") (pintype "passive"))
      (node (ref "J16") (pin "S3") (pinfunction "A-_S3") (pintype "bidirectional"))
    )
    (net (code "60") (name "P1V2") (class "Default")
      (node (ref "L8") (pin "1") (pinfunction "1_1") (pintype "passive"))
      (node (ref "L9") (pin "1") (pinfunction "1_1") (pintype "passive"))
    )
    (net (code "61") (name "P3V3") (class "Default")
      (node (ref "J16") (pin "P1") (pinfunction "V33_P1") (pintype "power_in"))
      (node (ref "J16") (pin "P2") (pinfunction "V33_P2") (pintype "power_in"))
      (node (ref "J16") (pin "P3") (pinfunction "V33_P3") (pintype "power_in"))
    )
    (net (code "62") (name "P5V_VME") (class "Default")
      (node (ref "J16") (pin "P7") (pinfunction "V5_P7") (pintype "power_in"))
      (node (ref "J16") (pin "P8") (pinfunction "V5_P8") (pintype "power_in"))
      (node (ref "J16") (pin "P9") (pinfunction "V5_P9") (pintype "power_in"))
    )
    (net (code "63") (name "unconnected-(IC19K-MGTREFCLK0N_123-PadC18)") (class "Default")
      (node (ref "IC19") (pin "C18") (pinfunction "MGTREFCLK0N_123_C18") (pintype "input+no_connect"))
    )
    (net (code "64") (name "unconnected-(IC19K-MGTREFCLK0P_123-PadD18)") (class "Default")
      (node (ref "IC19") (pin "D18") (pinfunction "MGTREFCLK0P_123_D18") (pintype "input+no_connect"))
    )
    (net (code "65") (name "unconnected-(IC19L-MGTREFCLK1N_245-PadAH14)") (class "Default")
      (node (ref "IC19") (pin "AH14") (pinfunction "MGTREFCLK1N_245_AH14") (pintype "input+no_connect"))
    )
    (net (code "66") (name "unconnected-(IC19L-MGTREFCLK1P_245-PadAG14)") (class "Default")
      (node (ref "IC19") (pin "AG14") (pinfunction "MGTREFCLK1P_245_AG14") (pintype "input+no_connect"))
    )
    (net (code "67") (name "unconnected-(IC19M-MGTREFCLK1N_267-PadAK19)") (class "Default")
      (node (ref "IC19") (pin "AK19") (pinfunction "MGTREFCLK1N_267_AK19") (pintype "input+no_connect"))
    )
    (net (code "68") (name "unconnected-(IC19M-MGTREFCLK1P_267-PadAJ19)") (class "Default")
      (node (ref "IC19") (pin "AJ19") (pinfunction "MGTREFCLK1P_267_AJ19") (pintype "input+no_connect"))
    )
    (net (code "69") (name "unconnected-(IC19M-MGTRXN1_267-PadAH22)") (class "Default")
      (node (ref "IC19") (pin "AH22") (pinfunction "MGTRXN1_267_AH22") (pintype "input+no_connect"))
    )
    (net (code "70") (name "unconnected-(IC19M-MGTRXP1_267-PadAG22)") (class "Default")
      (node (ref "IC19") (pin "AG22") (pinfunction "MGTRXP1_267_AG22") (pintype "input+no_connect"))
    )
    (net (code "71") (name "unconnected-(IC19M-MGTTXN1_267-PadAK23)") (class "Default")
      (node (ref "IC19") (pin "AK23") (pinfunction "MGTTXN1_267_AK23") (pintype "output"))
    )
    (net (code "72") (name "unconnected-(IC19M-MGTTXP1_267-PadAJ23)") (class "Default")
      (node (ref "IC19") (pin "AJ23") (pinfunction "MGTTXP1_267_AJ23") (pintype "output"))
    )
    (net (code "73") (name "unconnected-(J16-B+-PadS6)") (class "Default")
      (node (ref "J16") (pin "S6") (pinfunction "B+_S6") (pintype "bidirectional"))
    )
    (net (code "74") (name "unconnected-(J16-B--PadS5)") (class "Default")
      (node (ref "J16") (pin "S5") (pinfunction "B-_S5") (pintype "bidirectional"))
    )
    (net (code "75") (name "unconnected-(J16-RES-PadP11)") (class "Default")
      (node (ref "J16") (pin "P11") (pinfunction "RES_P11") (pintype "bidirectional"))
    )
    (net (code "76") (name "unconnected-(J16-V12-PadP13)") (class "Default")
      (node (ref "J16") (pin "P13") (pinfunction "V12_P13") (pintype "power_in"))
    )
    (net (code "77") (name "unconnected-(J16-V12-PadP14)") (class "Default")
      (node (ref "J16") (pin "P14") (pinfunction "V12_P14") (pintype "power_in"))
    )
    (net (code "78") (name "unconnected-(J16-V12-PadP15)") (class "Default")
      (node (ref "J16") (pin "P15") (pinfunction "V12_P15") (pintype "power_in"))
    )
  )
)
